# Sheet2.net
KiCad netlist of a schematic drawn in Altium Designer
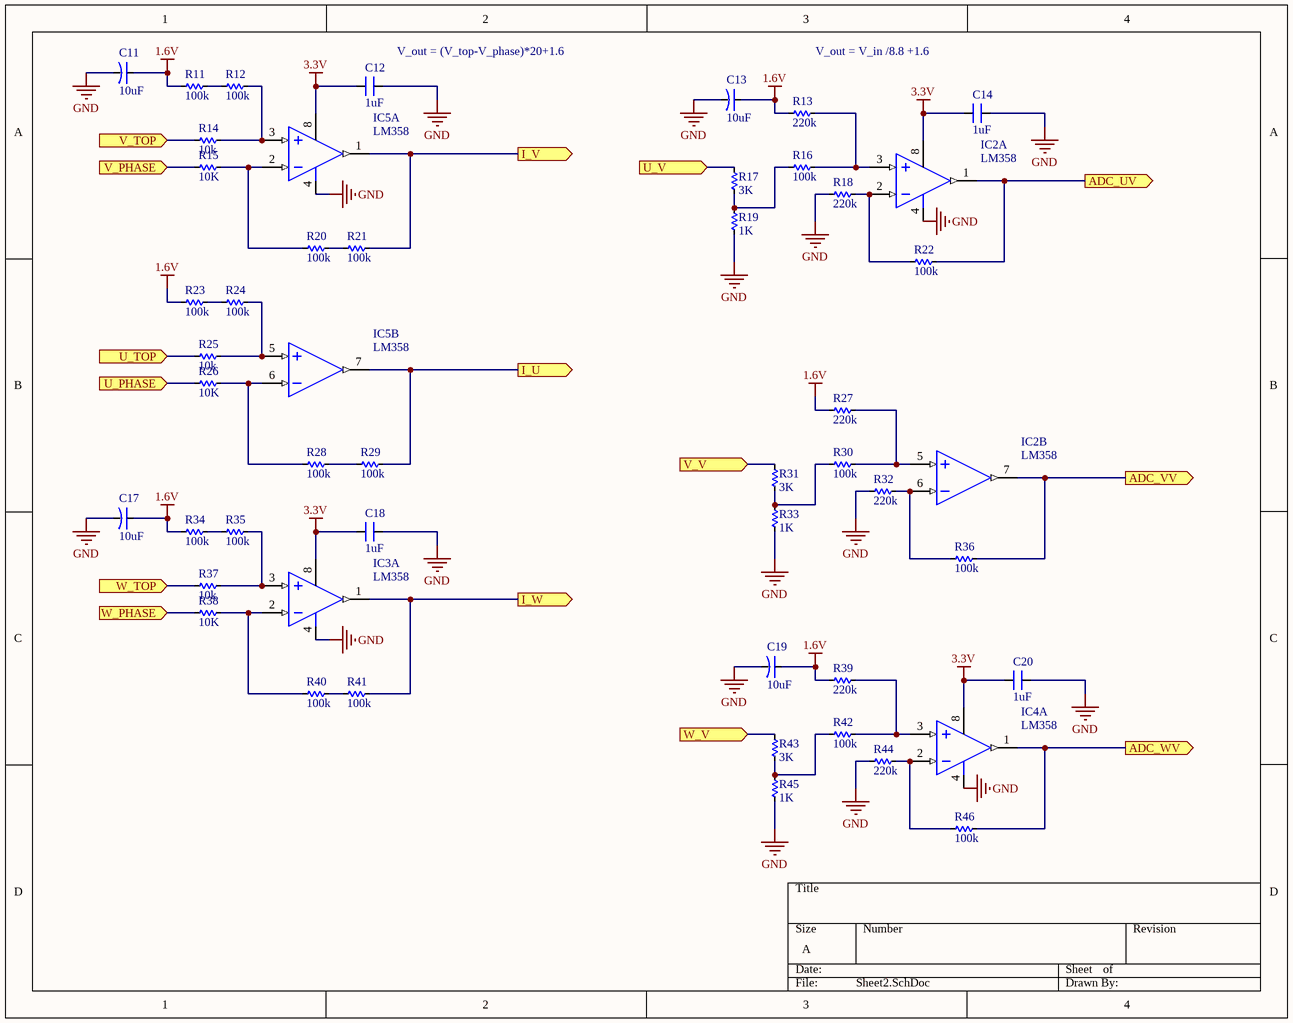
[diagram p0: Sheet2.SchDoc]

(export (version "E")
  (design (tool "Eeschema 10.0.6"))
  (components
    (comp (ref "C11")
      (value "10uF")
      (footprint "CA-ALU-5R")
      (description "Capacitor (Semiconductor SIM Model)")
      (fields (field (name "PUBLISHER") "Altium Limited"))
      (libsource (lib "LIBRARY") (part "CN-ALU-DIP"))
    )
    (comp (ref "C12")
      (value "1uF")
      (footprint "CN1")
      (description "Cap np  1pF - 472pF")
      (libsource (lib "syhaunguyen") (part "CN1"))
    )
    (comp (ref "C13")
      (value "10uF")
      (footprint "CA-ALU-5R")
      (description "Capacitor (Semiconductor SIM Model)")
      (fields (field (name "PUBLISHER") "Altium Limited"))
      (libsource (lib "LIBRARY") (part "CN-ALU-DIP"))
    )
    (comp (ref "C14")
      (value "1uF")
      (footprint "CN1")
      (description "Cap np  1pF - 472pF")
      (libsource (lib "syhaunguyen") (part "CN1"))
    )
    (comp (ref "C17")
      (value "10uF")
      (footprint "CA-ALU-5R")
      (description "Capacitor (Semiconductor SIM Model)")
      (fields (field (name "PUBLISHER") "Altium Limited"))
      (libsource (lib "LIBRARY") (part "CN-ALU-DIP"))
    )
    (comp (ref "C18")
      (value "1uF")
      (footprint "CN1")
      (description "Cap np  1pF - 472pF")
      (libsource (lib "syhaunguyen") (part "CN1"))
    )
    (comp (ref "C19")
      (value "10uF")
      (footprint "CA-ALU-5R")
      (description "Capacitor (Semiconductor SIM Model)")
      (fields (field (name "PUBLISHER") "Altium Limited"))
      (libsource (lib "LIBRARY") (part "CN-ALU-DIP"))
    )
    (comp (ref "C20")
      (value "1uF")
      (footprint "CN1")
      (description "Cap np  1pF - 472pF")
      (libsource (lib "syhaunguyen") (part "CN1"))
    )
    (comp (ref "IC2")
      (value "LM358")
      (footprint "DIP8")
      (description "Low-Power Dual Operational Amplifier")
      (libsource (lib "LIBRARY") (part "LM358"))
    )
    (comp (ref "IC3")
      (value "LM358")
      (footprint "DIP8")
      (description "Low-Power Dual Operational Amplifier")
      (libsource (lib "LIBRARY") (part "LM358"))
    )
    (comp (ref "IC4")
      (value "LM358")
      (footprint "DIP8")
      (description "Low-Power Dual Operational Amplifier")
      (libsource (lib "LIBRARY") (part "LM358"))
    )
    (comp (ref "IC5")
      (value "LM358")
      (footprint "DIP8")
      (description "Low-Power Dual Operational Amplifier")
      (libsource (lib "LIBRARY") (part "LM358"))
    )
    (comp (ref "R11")
      (value "100k")
      (footprint "RES-1/2W")
      (description "Res")
      (fields
        (field (name "MANUFACTURER") "Generic Components")
        (field (name "PUBLISHER") "Altium Hobart Technology Centre")
      )
      (libsource (lib "LIBRARY1") (part "Res"))
    )
    (comp (ref "R12")
      (value "100k")
      (footprint "RES-1/2W")
      (description "Res")
      (fields
        (field (name "MANUFACTURER") "Generic Components")
        (field (name "PUBLISHER") "Altium Hobart Technology Centre")
      )
      (libsource (lib "LIBRARY1") (part "Res"))
    )
    (comp (ref "R13")
      (value "220k")
      (footprint "RES-1/2W")
      (description "Res")
      (fields
        (field (name "MANUFACTURER") "Generic Components")
        (field (name "PUBLISHER") "Altium Hobart Technology Centre")
      )
      (libsource (lib "LIBRARY1") (part "Res"))
    )
    (comp (ref "R14")
      (value "10k")
      (footprint "RES-1/2W")
      (description "Res")
      (fields
        (field (name "MANUFACTURER") "Generic Components")
        (field (name "PUBLISHER") "Altium Hobart Technology Centre")
      )
      (libsource (lib "LIBRARY1") (part "Res"))
    )
    (comp (ref "R15")
      (value "10K")
      (footprint "RES-1/2W")
      (description "Res")
      (fields
        (field (name "MANUFACTURER") "Generic Components")
        (field (name "PUBLISHER") "Altium Hobart Technology Centre")
      )
      (libsource (lib "LIBRARY1") (part "Res"))
    )
    (comp (ref "R16")
      (value "100k")
      (footprint "RES-1/2W")
      (description "Res")
      (fields
        (field (name "MANUFACTURER") "Generic Components")
        (field (name "PUBLISHER") "Altium Hobart Technology Centre")
      )
      (libsource (lib "LIBRARY1") (part "Res"))
    )
    (comp (ref "R17")
      (value "3K")
      (footprint "RES-1/2W")
      (description "Res")
      (fields
        (field (name "MANUFACTURER") "Generic Components")
        (field (name "PUBLISHER") "Altium Hobart Technology Centre")
      )
      (libsource (lib "LIBRARY1") (part "Res"))
    )
    (comp (ref "R18")
      (value "220k")
      (footprint "RES-1/2W")
      (description "Res")
      (fields
        (field (name "MANUFACTURER") "Generic Components")
        (field (name "PUBLISHER") "Altium Hobart Technology Centre")
      )
      (libsource (lib "LIBRARY1") (part "Res"))
    )
    (comp (ref "R19")
      (value "1K")
      (footprint "RES-1/2W")
      (description "Res")
      (fields
        (field (name "MANUFACTURER") "Generic Components")
        (field (name "PUBLISHER") "Altium Hobart Technology Centre")
      )
      (libsource (lib "LIBRARY1") (part "Res"))
    )
    (comp (ref "R20")
      (value "100k")
      (footprint "RES-1/2W")
      (description "Res")
      (fields
        (field (name "MANUFACTURER") "Generic Components")
        (field (name "PUBLISHER") "Altium Hobart Technology Centre")
      )
      (libsource (lib "LIBRARY1") (part "Res"))
    )
    (comp (ref "R21")
      (value "100k")
      (footprint "RES-1/2W")
      (description "Res")
      (fields
        (field (name "MANUFACTURER") "Generic Components")
        (field (name "PUBLISHER") "Altium Hobart Technology Centre")
      )
      (libsource (lib "LIBRARY1") (part "Res"))
    )
    (comp (ref "R22")
      (value "100k")
      (footprint "RES-1/2W")
      (description "Res")
      (fields
        (field (name "MANUFACTURER") "Generic Components")
        (field (name "PUBLISHER") "Altium Hobart Technology Centre")
      )
      (libsource (lib "LIBRARY1") (part "Res"))
    )
    (comp (ref "R23")
      (value "100k")
      (footprint "RES-1/2W")
      (description "Res")
      (fields
        (field (name "MANUFACTURER") "Generic Components")
        (field (name "PUBLISHER") "Altium Hobart Technology Centre")
      )
      (libsource (lib "LIBRARY1") (part "Res"))
    )
    (comp (ref "R24")
      (value "100k")
      (footprint "RES-1/2W")
      (description "Res")
      (fields
        (field (name "MANUFACTURER") "Generic Components")
        (field (name "PUBLISHER") "Altium Hobart Technology Centre")
      )
      (libsource (lib "LIBRARY1") (part "Res"))
    )
    (comp (ref "R25")
      (value "10k")
      (footprint "RES-1/2W")
      (description "Res")
      (fields
        (field (name "MANUFACTURER") "Generic Components")
        (field (name "PUBLISHER") "Altium Hobart Technology Centre")
      )
      (libsource (lib "LIBRARY1") (part "Res"))
    )
    (comp (ref "R26")
      (value "10K")
      (footprint "RES-1/2W")
      (description "Res")
      (fields
        (field (name "MANUFACTURER") "Generic Components")
        (field (name "PUBLISHER") "Altium Hobart Technology Centre")
      )
      (libsource (lib "LIBRARY1") (part "Res"))
    )
    (comp (ref "R27")
      (value "220k")
      (footprint "RES-1/2W")
      (description "Res")
      (fields
        (field (name "MANUFACTURER") "Generic Components")
        (field (name "PUBLISHER") "Altium Hobart Technology Centre")
      )
      (libsource (lib "LIBRARY1") (part "Res"))
    )
    (comp (ref "R28")
      (value "100k")
      (footprint "RES-1/2W")
      (description "Res")
      (fields
        (field (name "MANUFACTURER") "Generic Components")
        (field (name "PUBLISHER") "Altium Hobart Technology Centre")
      )
      (libsource (lib "LIBRARY1") (part "Res"))
    )
    (comp (ref "R29")
      (value "100k")
      (footprint "RES-1/2W")
      (description "Res")
      (fields
        (field (name "MANUFACTURER") "Generic Components")
        (field (name "PUBLISHER") "Altium Hobart Technology Centre")
      )
      (libsource (lib "LIBRARY1") (part "Res"))
    )
    (comp (ref "R30")
      (value "100k")
      (footprint "RES-1/2W")
      (description "Res")
      (fields
        (field (name "MANUFACTURER") "Generic Components")
        (field (name "PUBLISHER") "Altium Hobart Technology Centre")
      )
      (libsource (lib "LIBRARY1") (part "Res"))
    )
    (comp (ref "R31")
      (value "3K")
      (footprint "RES-1/2W")
      (description "Res")
      (fields
        (field (name "MANUFACTURER") "Generic Components")
        (field (name "PUBLISHER") "Altium Hobart Technology Centre")
      )
      (libsource (lib "LIBRARY1") (part "Res"))
    )
    (comp (ref "R32")
      (value "220k")
      (footprint "RES-1/2W")
      (description "Res")
      (fields
        (field (name "MANUFACTURER") "Generic Components")
        (field (name "PUBLISHER") "Altium Hobart Technology Centre")
      )
      (libsource (lib "LIBRARY1") (part "Res"))
    )
    (comp (ref "R33")
      (value "1K")
      (footprint "RES-1/2W")
      (description "Res")
      (fields
        (field (name "MANUFACTURER") "Generic Components")
        (field (name "PUBLISHER") "Altium Hobart Technology Centre")
      )
      (libsource (lib "LIBRARY1") (part "Res"))
    )
    (comp (ref "R34")
      (value "100k")
      (footprint "RES-1/2W")
      (description "Res")
      (fields
        (field (name "MANUFACTURER") "Generic Components")
        (field (name "PUBLISHER") "Altium Hobart Technology Centre")
      )
      (libsource (lib "LIBRARY1") (part "Res"))
    )
    (comp (ref "R35")
      (value "100k")
      (footprint "RES-1/2W")
      (description "Res")
      (fields
        (field (name "MANUFACTURER") "Generic Components")
        (field (name "PUBLISHER") "Altium Hobart Technology Centre")
      )
      (libsource (lib "LIBRARY1") (part "Res"))
    )
    (comp (ref "R36")
      (value "100k")
      (footprint "RES-1/2W")
      (description "Res")
      (fields
        (field (name "MANUFACTURER") "Generic Components")
        (field (name "PUBLISHER") "Altium Hobart Technology Centre")
      )
      (libsource (lib "LIBRARY1") (part "Res"))
    )
    (comp (ref "R37")
      (value "10k")
      (footprint "RES-1/2W")
      (description "Res")
      (fields
        (field (name "MANUFACTURER") "Generic Components")
        (field (name "PUBLISHER") "Altium Hobart Technology Centre")
      )
      (libsource (lib "LIBRARY1") (part "Res"))
    )
    (comp (ref "R38")
      (value "10K")
      (footprint "RES-1/2W")
      (description "Res")
      (fields
        (field (name "MANUFACTURER") "Generic Components")
        (field (name "PUBLISHER") "Altium Hobart Technology Centre")
      )
      (libsource (lib "LIBRARY1") (part "Res"))
    )
    (comp (ref "R39")
      (value "220k")
      (footprint "RES-1/2W")
      (description "Res")
      (fields
        (field (name "MANUFACTURER") "Generic Components")
        (field (name "PUBLISHER") "Altium Hobart Technology Centre")
      )
      (libsource (lib "LIBRARY1") (part "Res"))
    )
    (comp (ref "R40")
      (value "100k")
      (footprint "RES-1/2W")
      (description "Res")
      (fields
        (field (name "MANUFACTURER") "Generic Components")
        (field (name "PUBLISHER") "Altium Hobart Technology Centre")
      )
      (libsource (lib "LIBRARY1") (part "Res"))
    )
    (comp (ref "R41")
      (value "100k")
      (footprint "RES-1/2W")
      (description "Res")
      (fields
        (field (name "MANUFACTURER") "Generic Components")
        (field (name "PUBLISHER") "Altium Hobart Technology Centre")
      )
      (libsource (lib "LIBRARY1") (part "Res"))
    )
    (comp (ref "R42")
      (value "100k")
      (footprint "RES-1/2W")
      (description "Res")
      (fields
        (field (name "MANUFACTURER") "Generic Components")
        (field (name "PUBLISHER") "Altium Hobart Technology Centre")
      )
      (libsource (lib "LIBRARY1") (part "Res"))
    )
    (comp (ref "R43")
      (value "3K")
      (footprint "RES-1/2W")
      (description "Res")
      (fields
        (field (name "MANUFACTURER") "Generic Components")
        (field (name "PUBLISHER") "Altium Hobart Technology Centre")
      )
      (libsource (lib "LIBRARY1") (part "Res"))
    )
    (comp (ref "R44")
      (value "220k")
      (footprint "RES-1/2W")
      (description "Res")
      (fields
        (field (name "MANUFACTURER") "Generic Components")
        (field (name "PUBLISHER") "Altium Hobart Technology Centre")
      )
      (libsource (lib "LIBRARY1") (part "Res"))
    )
    (comp (ref "R45")
      (value "1K")
      (footprint "RES-1/2W")
      (description "Res")
      (fields
        (field (name "MANUFACTURER") "Generic Components")
        (field (name "PUBLISHER") "Altium Hobart Technology Centre")
      )
      (libsource (lib "LIBRARY1") (part "Res"))
    )
    (comp (ref "R46")
      (value "100k")
      (footprint "RES-1/2W")
      (description "Res")
      (fields
        (field (name "MANUFACTURER") "Generic Components")
        (field (name "PUBLISHER") "Altium Hobart Technology Centre")
      )
      (libsource (lib "LIBRARY1") (part "Res"))
    )
  )
  (nets
    (net (code "1") (name "/ADC_UV") (class "Default")
      (node (ref "IC2") (pin "1") (pinfunction "OUT_1") (pintype "output"))
      (node (ref "R22") (pin "1") (pinfunction "1_1") (pintype "passive"))
    )
    (net (code "2") (name "/ADC_VV") (class "Default")
      (node (ref "IC2") (pin "7") (pinfunction "OUT_7") (pintype "output"))
      (node (ref "R36") (pin "1") (pinfunction "1_1") (pintype "passive"))
    )
    (net (code "3") (name "/ADC_WV") (class "Default")
      (node (ref "IC4") (pin "1") (pinfunction "OUT_1") (pintype "output"))
      (node (ref "R46") (pin "1") (pinfunction "1_1") (pintype "passive"))
    )
    (net (code "4") (name "/I_U") (class "Default")
      (node (ref "IC5") (pin "7") (pinfunction "OUT_7") (pintype "output"))
      (node (ref "R29") (pin "1") (pinfunction "1_1") (pintype "passive"))
    )
    (net (code "5") (name "/I_V") (class "Default")
      (node (ref "IC5") (pin "1") (pinfunction "OUT_1") (pintype "output"))
      (node (ref "R21") (pin "1") (pinfunction "1_1") (pintype "passive"))
    )
    (net (code "6") (name "/I_W") (class "Default")
      (node (ref "IC3") (pin "1") (pinfunction "OUT_1") (pintype "output"))
      (node (ref "R41") (pin "1") (pinfunction "1_1") (pintype "passive"))
    )
    (net (code "7") (name "/U_PHASE") (class "Default")
      (node (ref "R26") (pin "2") (pinfunction "2_2") (pintype "passive"))
    )
    (net (code "8") (name "/U_TOP") (class "Default")
      (node (ref "R25") (pin "2") (pinfunction "2_2") (pintype "passive"))
    )
    (net (code "9") (name "/U_V") (class "Default")
      (node (ref "R17") (pin "1") (pinfunction "1_1") (pintype "passive"))
    )
    (net (code "10") (name "/V_PHASE") (class "Default")
      (node (ref "R15") (pin "2") (pinfunction "2_2") (pintype "passive"))
    )
    (net (code "11") (name "/V_TOP") (class "Default")
      (node (ref "R14") (pin "2") (pinfunction "2_2") (pintype "passive"))
    )
    (net (code "12") (name "/V_V") (class "Default")
      (node (ref "R31") (pin "1") (pinfunction "1_1") (pintype "passive"))
    )
    (net (code "13") (name "/W_PHASE") (class "Default")
      (node (ref "R38") (pin "2") (pinfunction "2_2") (pintype "passive"))
    )
    (net (code "14") (name "/W_TOP") (class "Default")
      (node (ref "R37") (pin "2") (pinfunction "2_2") (pintype "passive"))
    )
    (net (code "15") (name "/W_V") (class "Default")
      (node (ref "R43") (pin "1") (pinfunction "1_1") (pintype "passive"))
    )
    (net (code "16") (name "1.6V") (class "Default")
      (node (ref "C11") (pin "1") (pinfunction "1_1") (pintype "passive"))
      (node (ref "C13") (pin "1") (pinfunction "1_1") (pintype "passive"))
      (node (ref "C17") (pin "1") (pinfunction "1_1") (pintype "passive"))
      (node (ref "C19") (pin "1") (pinfunction "1_1") (pintype "passive"))
      (node (ref "R11") (pin "2") (pinfunction "2_2") (pintype "passive"))
      (node (ref "R13") (pin "2") (pinfunction "2_2") (pintype "passive"))
      (node (ref "R23") (pin "2") (pinfunction "2_2") (pintype "passive"))
      (node (ref "R27") (pin "2") (pinfunction "2_2") (pintype "passive"))
      (node (ref "R34") (pin "2") (pinfunction "2_2") (pintype "passive"))
      (node (ref "R39") (pin "2") (pinfunction "2_2") (pintype "passive"))
    )
    (net (code "17") (name "3.3V") (class "Default")
      (node (ref "C12") (pin "1") (pinfunction "1_1") (pintype "passive"))
      (node (ref "C14") (pin "1") (pinfunction "1_1") (pintype "passive"))
      (node (ref "C18") (pin "1") (pinfunction "1_1") (pintype "passive"))
      (node (ref "C20") (pin "1") (pinfunction "1_1") (pintype "passive"))
      (node (ref "IC2") (pin "8") (pinfunction "+V_8") (pintype "passive"))
      (node (ref "IC3") (pin "8") (pinfunction "+V_8") (pintype "passive"))
      (node (ref "IC4") (pin "8") (pinfunction "+V_8") (pintype "passive"))
      (node (ref "IC5") (pin "8") (pinfunction "+V_8") (pintype "passive"))
    )
    (net (code "18") (name "GND") (class "Default")
      (node (ref "C11") (pin "2") (pinfunction "2_2") (pintype "passive"))
      (node (ref "C12") (pin "2") (pinfunction "2_2") (pintype "passive"))
      (node (ref "C13") (pin "2") (pinfunction "2_2") (pintype "passive"))
      (node (ref "C14") (pin "2") (pinfunction "2_2") (pintype "passive"))
      (node (ref "C17") (pin "2") (pinfunction "2_2") (pintype "passive"))
      (node (ref "C18") (pin "2") (pinfunction "2_2") (pintype "passive"))
      (node (ref "C19") (pin "2") (pinfunction "2_2") (pintype "passive"))
      (node (ref "C20") (pin "2") (pinfunction "2_2") (pintype "passive"))
      (node (ref "IC2") (pin "4") (pinfunction "-V_4") (pintype "passive"))
      (node (ref "IC3") (pin "4") (pinfunction "-V_4") (pintype "passive"))
      (node (ref "IC4") (pin "4") (pinfunction "-V_4") (pintype "passive"))
      (node (ref "IC5") (pin "4") (pinfunction "-V_4") (pintype "passive"))
      (node (ref "R18") (pin "2") (pinfunction "2_2") (pintype "passive"))
      (node (ref "R19") (pin "2") (pinfunction "2_2") (pintype "passive"))
      (node (ref "R32") (pin "2") (pinfunction "2_2") (pintype "passive"))
      (node (ref "R33") (pin "2") (pinfunction "2_2") (pintype "passive"))
      (node (ref "R44") (pin "2") (pinfunction "2_2") (pintype "passive"))
      (node (ref "R45") (pin "2") (pinfunction "2_2") (pintype "passive"))
    )
    (net (code "19") (name "Net-(IC2A-IN+)") (class "Default")
      (node (ref "IC2") (pin "3") (pinfunction "IN+_3") (pintype "input"))
      (node (ref "R13") (pin "1") (pinfunction "1_1") (pintype "passive"))
      (node (ref "R16") (pin "1") (pinfunction "1_1") (pintype "passive"))
    )
    (net (code "20") (name "Net-(IC2A-IN-)") (class "Default")
      (node (ref "IC2") (pin "2") (pinfunction "IN-_2") (pintype "input"))
      (node (ref "R18") (pin "1") (pinfunction "1_1") (pintype "passive"))
      (node (ref "R22") (pin "2") (pinfunction "2_2") (pintype "passive"))
    )
    (net (code "21") (name "Net-(IC2B-IN+)") (class "Default")
      (node (ref "IC2") (pin "5") (pinfunction "IN+_5") (pintype "input"))
      (node (ref "R27") (pin "1") (pinfunction "1_1") (pintype "passive"))
      (node (ref "R30") (pin "1") (pinfunction "1_1") (pintype "passive"))
    )
    (net (code "22") (name "Net-(IC2B-IN-)") (class "Default")
      (node (ref "IC2") (pin "6") (pinfunction "IN-_6") (pintype "input"))
      (node (ref "R32") (pin "1") (pinfunction "1_1") (pintype "passive"))
      (node (ref "R36") (pin "2") (pinfunction "2_2") (pintype "passive"))
    )
    (net (code "23") (name "Net-(IC3A-IN+)") (class "Default")
      (node (ref "IC3") (pin "3") (pinfunction "IN+_3") (pintype "input"))
      (node (ref "R35") (pin "1") (pinfunction "1_1") (pintype "passive"))
      (node (ref "R37") (pin "1") (pinfunction "1_1") (pintype "passive"))
    )
    (net (code "24") (name "Net-(IC3A-IN-)") (class "Default")
      (node (ref "IC3") (pin "2") (pinfunction "IN-_2") (pintype "input"))
      (node (ref "R38") (pin "1") (pinfunction "1_1") (pintype "passive"))
      (node (ref "R40") (pin "2") (pinfunction "2_2") (pintype "passive"))
    )
    (net (code "25") (name "Net-(IC4A-IN+)") (class "Default")
      (node (ref "IC4") (pin "3") (pinfunction "IN+_3") (pintype "input"))
      (node (ref "R39") (pin "1") (pinfunction "1_1") (pintype "passive"))
      (node (ref "R42") (pin "1") (pinfunction "1_1") (pintype "passive"))
    )
    (net (code "26") (name "Net-(IC4A-IN-)") (class "Default")
      (node (ref "IC4") (pin "2") (pinfunction "IN-_2") (pintype "input"))
      (node (ref "R44") (pin "1") (pinfunction "1_1") (pintype "passive"))
      (node (ref "R46") (pin "2") (pinfunction "2_2") (pintype "passive"))
    )
    (net (code "27") (name "Net-(IC5A-IN+)") (class "Default")
      (node (ref "IC5") (pin "3") (pinfunction "IN+_3") (pintype "input"))
      (node (ref "R12") (pin "1") (pinfunction "1_1") (pintype "passive"))
      (node (ref "R14") (pin "1") (pinfunction "1_1") (pintype "passive"))
    )
    (net (code "28") (name "Net-(IC5A-IN-)") (class "Default")
      (node (ref "IC5") (pin "2") (pinfunction "IN-_2") (pintype "input"))
      (node (ref "R15") (pin "1") (pinfunction "1_1") (pintype "passive"))
      (node (ref "R20") (pin "2") (pinfunction "2_2") (pintype "passive"))
    )
    (net (code "29") (name "Net-(IC5B-IN+)") (class "Default")
      (node (ref "IC5") (pin "5") (pinfunction "IN+_5") (pintype "input"))
      (node (ref "R24") (pin "1") (pinfunction "1_1") (pintype "passive"))
      (node (ref "R25") (pin "1") (pinfunction "1_1") (pintype "passive"))
    )
    (net (code "30") (name "Net-(IC5B-IN-)") (class "Default")
      (node (ref "IC5") (pin "6") (pinfunction "IN-_6") (pintype "input"))
      (node (ref "R26") (pin "1") (pinfunction "1_1") (pintype "passive"))
      (node (ref "R28") (pin "2") (pinfunction "2_2") (pintype "passive"))
    )
    (net (code "31") (name "Net-(R11-Pad1)") (class "Default")
      (node (ref "R11") (pin "1") (pinfunction "1_1") (pintype "passive"))
      (node (ref "R12") (pin "2") (pinfunction "2_2") (pintype "passive"))
    )
    (net (code "32") (name "Net-(R16-Pad2)") (class "Default")
      (node (ref "R16") (pin "2") (pinfunction "2_2") (pintype "passive"))
      (node (ref "R17") (pin "2") (pinfunction "2_2") (pintype "passive"))
      (node (ref "R19") (pin "1") (pinfunction "1_1") (pintype "passive"))
    )
    (net (code "33") (name "Net-(R20-Pad1)") (class "Default")
      (node (ref "R20") (pin "1") (pinfunction "1_1") (pintype "passive"))
      (node (ref "R21") (pin "2") (pinfunction "2_2") (pintype "passive"))
    )
    (net (code "34") (name "Net-(R23-Pad1)") (class "Default")
      (node (ref "R23") (pin "1") (pinfunction "1_1") (pintype "passive"))
      (node (ref "R24") (pin "2") (pinfunction "2_2") (pintype "passive"))
    )
    (net (code "35") (name "Net-(R28-Pad1)") (class "Default")
      (node (ref "R28") (pin "1") (pinfunction "1_1") (pintype "passive"))
      (node (ref "R29") (pin "2") (pinfunction "2_2") (pintype "passive"))
    )
    (net (code "36") (name "Net-(R30-Pad2)") (class "Default")
      (node (ref "R30") (pin "2") (pinfunction "2_2") (pintype "passive"))
      (node (ref "R31") (pin "2") (pinfunction "2_2") (pintype "passive"))
      (node (ref "R33") (pin "1") (pinfunction "1_1") (pintype "passive"))
    )
    (net (code "37") (name "Net-(R34-Pad1)") (class "Default")
      (node (ref "R34") (pin "1") (pinfunction "1_1") (pintype "passive"))
      (node (ref "R35") (pin "2") (pinfunction "2_2") (pintype "passive"))
    )
    (net (code "38") (name "Net-(R40-Pad1)") (class "Default")
      (node (ref "R40") (pin "1") (pinfunction "1_1") (pintype "passive"))
      (node (ref "R41") (pin "2") (pinfunction "2_2") (pintype "passive"))
    )
    (net (code "39") (name "Net-(R42-Pad2)") (class "Default")
      (node (ref "R42") (pin "2") (pinfunction "2_2") (pintype "passive"))
      (node (ref "R43") (pin "2") (pinfunction "2_2") (pintype "passive"))
      (node (ref "R45") (pin "1") (pinfunction "1_1") (pintype "passive"))
    )
  )
)
